# eps_imu.net
KiCad netlist of a schematic drawn in Altium Designer
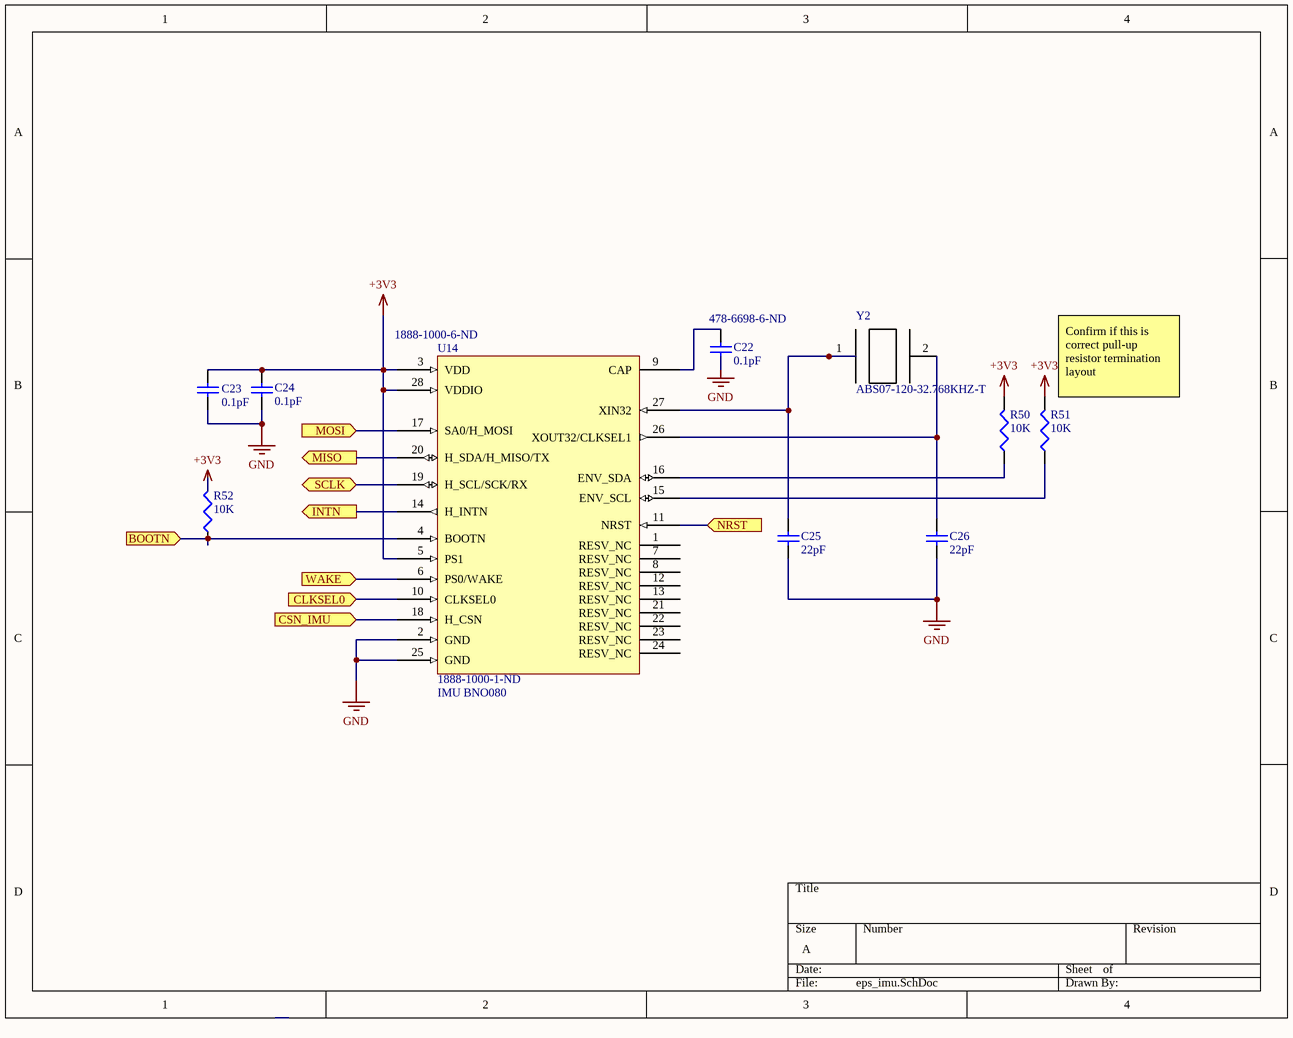
[diagram p0: eps_imu.SchDoc]

(export (version "E")
  (design (tool "Eeschema 10.0.6"))
  (components
    (comp (ref "C22")
      (value "0.1pF")
      (footprint "1608[0603]")
      (description "Capacitor (Semiconductor SIM Model)")
      (fields
        (field (name "SUPPLIER PART NUMBER 1") "478-6698-6-ND")
        (field (name "PUBLISHER") "Altium Limited")
      )
      (libsource (lib "Miscellaneous Devices") (part "Cap Semi"))
    )
    (comp (ref "C23")
      (value "0.1pF")
      (footprint "1608[0603]")
      (description "Capacitor (Semiconductor SIM Model)")
      (fields (field (name "PUBLISHER") "Altium Limited"))
      (libsource (lib "Miscellaneous Devices") (part "Cap Semi"))
    )
    (comp (ref "C24")
      (value "0.1pF")
      (footprint "1608[0603]")
      (description "Capacitor (Semiconductor SIM Model)")
      (fields (field (name "PUBLISHER") "Altium Limited"))
      (libsource (lib "Miscellaneous Devices") (part "Cap Semi"))
    )
    (comp (ref "C25")
      (value "22pF")
      (footprint "1608[0603]")
      (description "Capacitor (Semiconductor SIM Model)")
      (fields (field (name "PUBLISHER") "Altium Limited"))
      (libsource (lib "Miscellaneous Devices") (part "Cap Semi"))
    )
    (comp (ref "C26")
      (value "22pF")
      (footprint "1608[0603]")
      (description "Capacitor (Semiconductor SIM Model)")
      (fields (field (name "PUBLISHER") "Altium Limited"))
      (libsource (lib "Miscellaneous Devices") (part "Cap Semi"))
    )
    (comp (ref "R50")
      (value "10K")
      (footprint "J1-0603")
      (description "Resistor")
      (fields (field (name "PUBLISHER") "Altium Limited"))
      (libsource (lib "Miscellaneous Devices") (part "Res3"))
    )
    (comp (ref "R51")
      (value "10K")
      (footprint "J1-0603")
      (description "Resistor")
      (fields (field (name "PUBLISHER") "Altium Limited"))
      (libsource (lib "Miscellaneous Devices") (part "Res3"))
    )
    (comp (ref "R52")
      (value "10K")
      (footprint "J1-0603")
      (description "Resistor")
      (fields (field (name "PUBLISHER") "Altium Limited"))
      (libsource (lib "Miscellaneous Devices") (part "Res3"))
    )
    (comp (ref "U14")
      (value "IMU BNO080")
      (footprint "1888-1000-1-ND")
      (description "ACCEL/GYRO/MAG I2C 32BIT")
      (fields (field (name "SUPPLIER PART NUMBER 1") "1888-1000-6-ND"))
      (libsource (lib "ICs") (part "IMU BNO080"))
    )
    (comp (ref "Y2")
      (value "ABS07-120-32.768KHZ-T")
      (footprint "ABS07-120-32.768")
      (fields (field (name "MF") "Abracon"))
      (libsource (lib "ABS07-120-32.768KHZ-T") (part "ABS07-120-32.768KHZ-T"))
    )
  )
  (nets
    (net (code "1") (name "+3V3") (class "Default")
      (node (ref "C23") (pin "2") (pinfunction "2_2") (pintype "passive"))
      (node (ref "C24") (pin "2") (pinfunction "2_2") (pintype "passive"))
      (node (ref "R50") (pin "2") (pinfunction "2_2") (pintype "passive"))
      (node (ref "R51") (pin "2") (pinfunction "2_2") (pintype "passive"))
      (node (ref "R52") (pin "2") (pinfunction "2_2") (pintype "passive"))
      (node (ref "U14") (pin "28") (pinfunction "VDDIO_28") (pintype "input"))
      (node (ref "U14") (pin "3") (pinfunction "VDD_3") (pintype "input"))
      (node (ref "U14") (pin "5") (pinfunction "PS1_5") (pintype "input"))
    )
    (net (code "2") (name "/BOOTN") (class "Default")
      (node (ref "R52") (pin "1") (pinfunction "1_1") (pintype "passive"))
      (node (ref "U14") (pin "4") (pinfunction "BOOTN_4") (pintype "input"))
    )
    (net (code "3") (name "/CLKSEL0") (class "Default")
      (node (ref "U14") (pin "10") (pinfunction "CLKSEL0_10") (pintype "input"))
    )
    (net (code "4") (name "/CSN_IMU") (class "Default")
      (node (ref "U14") (pin "18") (pinfunction "H_CSN_18") (pintype "input"))
    )
    (net (code "5") (name "/INTN") (class "Default")
      (node (ref "U14") (pin "14") (pinfunction "H_INTN_14") (pintype "output"))
    )
    (net (code "6") (name "/MISO") (class "Default")
      (node (ref "U14") (pin "20") (pinfunction "H_SDA/H_MISO/TX_20") (pintype "bidirectional"))
    )
    (net (code "7") (name "/MOSI") (class "Default")
      (node (ref "U14") (pin "17") (pinfunction "SA0/H_MOSI_17") (pintype "input"))
    )
    (net (code "8") (name "/NRST") (class "Default")
      (node (ref "U14") (pin "11") (pinfunction "NRST_11") (pintype "input"))
    )
    (net (code "9") (name "/SCLK") (class "Default")
      (node (ref "U14") (pin "19") (pinfunction "H_SCL/SCK/RX_19") (pintype "bidirectional"))
    )
    (net (code "10") (name "/WAKE") (class "Default")
      (node (ref "U14") (pin "6") (pinfunction "PS0/WAKE_6") (pintype "input"))
    )
    (net (code "11") (name "GND") (class "Default")
      (node (ref "C22") (pin "1") (pinfunction "1_1") (pintype "passive"))
      (node (ref "C23") (pin "1") (pinfunction "1_1") (pintype "passive"))
      (node (ref "C24") (pin "1") (pinfunction "1_1") (pintype "passive"))
      (node (ref "C25") (pin "1") (pinfunction "1_1") (pintype "passive"))
      (node (ref "C26") (pin "1") (pinfunction "1_1") (pintype "passive"))
      (node (ref "U14") (pin "2") (pinfunction "GND_2") (pintype "input"))
      (node (ref "U14") (pin "25") (pinfunction "GND_25") (pintype "input"))
    )
    (net (code "12") (name "Net-(U14-CAP)") (class "Default")
      (node (ref "C22") (pin "2") (pinfunction "2_2") (pintype "passive"))
      (node (ref "U14") (pin "9") (pinfunction "CAP_9") (pintype "passive"))
    )
    (net (code "13") (name "Net-(U14-ENV_SCL)") (class "Default")
      (node (ref "R51") (pin "1") (pinfunction "1_1") (pintype "passive"))
      (node (ref "U14") (pin "15") (pinfunction "ENV_SCL_15") (pintype "bidirectional"))
    )
    (net (code "14") (name "Net-(U14-ENV_SDA)") (class "Default")
      (node (ref "R50") (pin "1") (pinfunction "1_1") (pintype "passive"))
      (node (ref "U14") (pin "16") (pinfunction "ENV_SDA_16") (pintype "bidirectional"))
    )
    (net (code "15") (name "Net-(U14-XIN32)") (class "Default")
      (node (ref "C25") (pin "2") (pinfunction "2_2") (pintype "passive"))
      (node (ref "U14") (pin "27") (pinfunction "XIN32_27") (pintype "input"))
      (node (ref "Y2") (pin "1") (pinfunction "1_1") (pintype "passive"))
    )
    (net (code "16") (name "Net-(U14-XOUT32{slash}CLKSEL1)") (class "Default")
      (node (ref "C26") (pin "2") (pinfunction "2_2") (pintype "passive"))
      (node (ref "U14") (pin "26") (pinfunction "XOUT32/CLKSEL1_26") (pintype "output"))
      (node (ref "Y2") (pin "2") (pinfunction "2_2") (pintype "passive"))
    )
    (net (code "17") (name "unconnected-(U14-RESV_NC-Pad1)") (class "Default")
      (node (ref "U14") (pin "1") (pinfunction "RESV_NC_1") (pintype "passive"))
    )
    (net (code "18") (name "unconnected-(U14-RESV_NC-Pad7)") (class "Default")
      (node (ref "U14") (pin "7") (pinfunction "RESV_NC_7") (pintype "passive"))
    )
    (net (code "19") (name "unconnected-(U14-RESV_NC-Pad8)") (class "Default")
      (node (ref "U14") (pin "8") (pinfunction "RESV_NC_8") (pintype "passive"))
    )
    (net (code "20") (name "unconnected-(U14-RESV_NC-Pad12)") (class "Default")
      (node (ref "U14") (pin "12") (pinfunction "RESV_NC_12") (pintype "passive"))
    )
    (net (code "21") (name "unconnected-(U14-RESV_NC-Pad13)") (class "Default")
      (node (ref "U14") (pin "13") (pinfunction "RESV_NC_13") (pintype "passive"))
    )
    (net (code "22") (name "unconnected-(U14-RESV_NC-Pad21)") (class "Default")
      (node (ref "U14") (pin "21") (pinfunction "RESV_NC_21") (pintype "passive"))
    )
    (net (code "23") (name "unconnected-(U14-RESV_NC-Pad22)") (class "Default")
      (node (ref "U14") (pin "22") (pinfunction "RESV_NC_22") (pintype "passive"))
    )
    (net (code "24") (name "unconnected-(U14-RESV_NC-Pad23)") (class "Default")
      (node (ref "U14") (pin "23") (pinfunction "RESV_NC_23") (pintype "passive"))
    )
    (net (code "25") (name "unconnected-(U14-RESV_NC-Pad24)") (class "Default")
      (node (ref "U14") (pin "24") (pinfunction "RESV_NC_24") (pintype "passive"))
    )
  )
)
